# Meshtastic-DIY.net
KiCad netlist of a schematic drawn in EAGLE
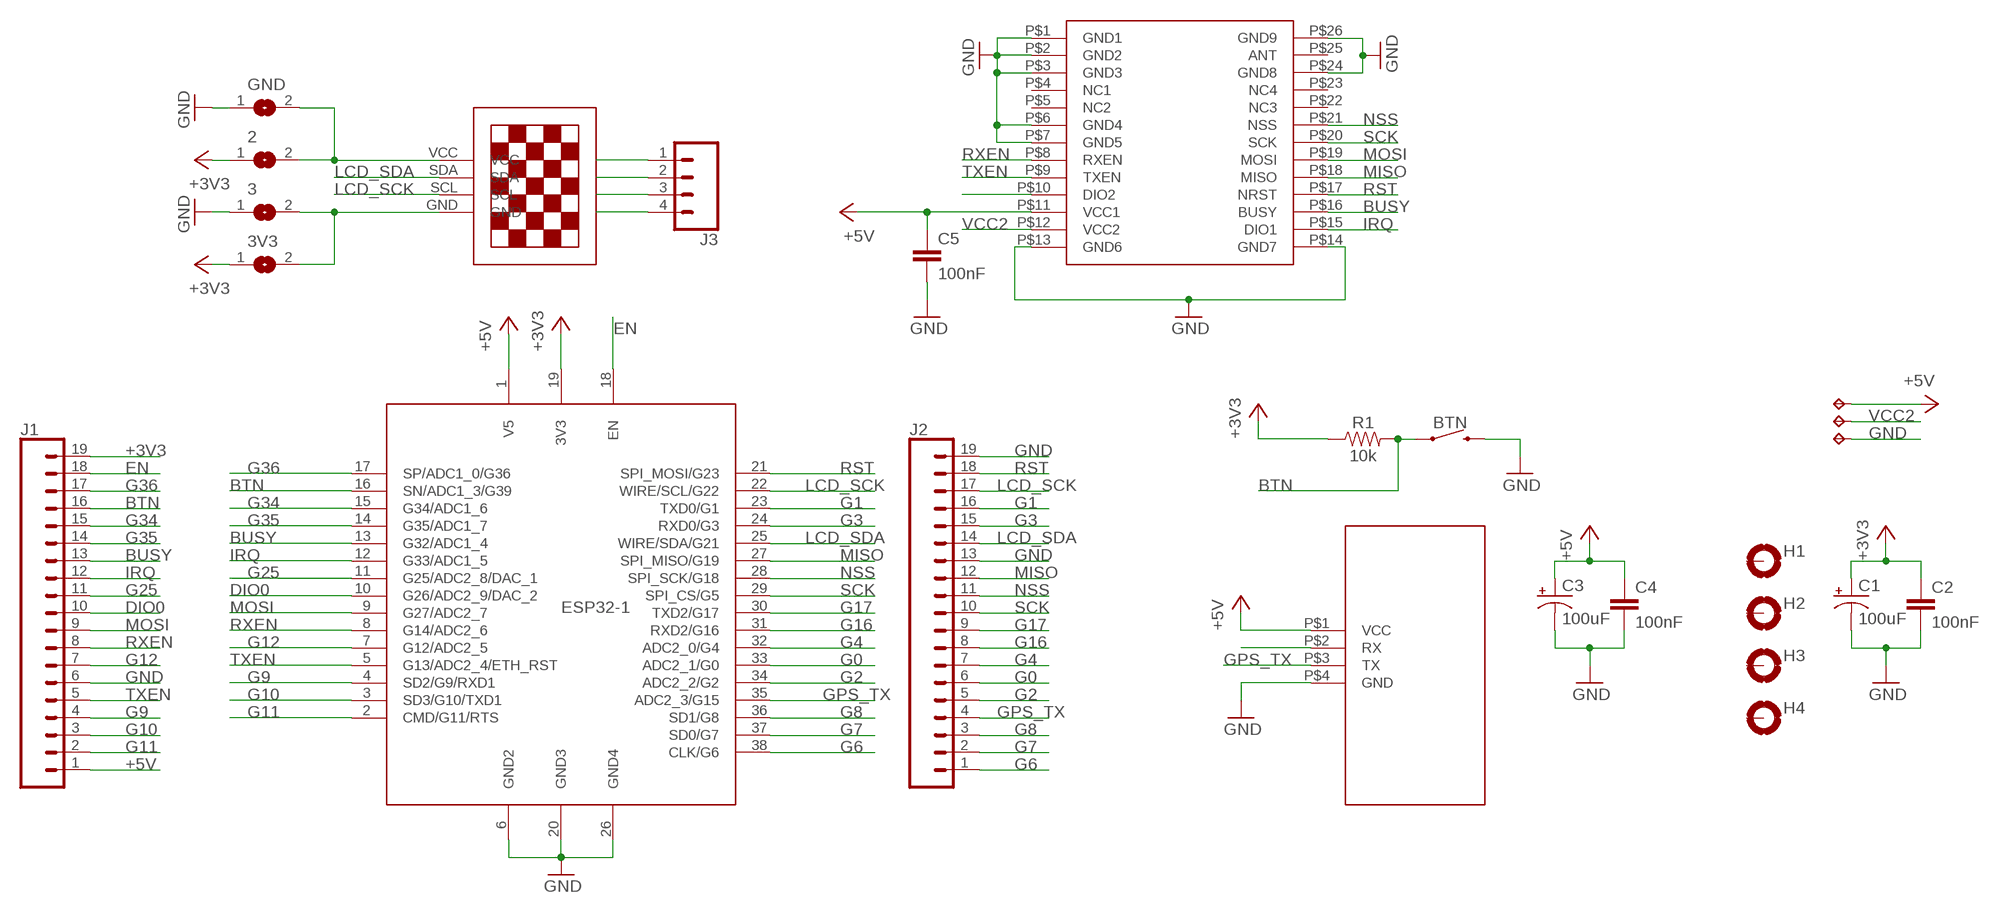
[diagram p0: schematic, sheet 1]

(export (version "E")
  (design (tool "Eeschema 10.0.6"))
  (components
    (comp (ref "2") (value "SJ") (footprint "eagle-import:SJ") (libsource (lib "eagle-import") (part "SJ")))
    (comp (ref "3") (value "SJ") (footprint "eagle-import:SJ") (libsource (lib "eagle-import") (part "SJ")))
    (comp (ref "3V3") (value "SJ") (footprint "eagle-import:SJ") (libsource (lib "eagle-import") (part "SJ")))
    (comp (ref "BTN")
      (value "MOMENTARY-SWITCH-SPST-PTH-6.0MM")
      (footprint "eagle-import:TACTILE_SWITCH_PTH_6.0MM")
      (libsource (lib "eagle-import") (part "MOMENTARY-SWITCH-SPST-PTH-6.0MM"))
    )
    (comp (ref "C1")
      (value "100uF")
      (footprint "eagle-import:EIA7343")
      (libsource (lib "eagle-import") (part "100UF-POLAR-EIA7343-10V-10%(TANT)"))
    )
    (comp (ref "C2")
      (value "100nF")
      (footprint "eagle-import:0805")
      (libsource (lib "eagle-import") (part "0.33UF/330NF-0805-50V-10%"))
    )
    (comp (ref "C3")
      (value "100uF")
      (footprint "eagle-import:EIA7343")
      (libsource (lib "eagle-import") (part "100UF-POLAR-EIA7343-10V-10%(TANT)"))
    )
    (comp (ref "C4")
      (value "100nF")
      (footprint "eagle-import:0805")
      (libsource (lib "eagle-import") (part "0.33UF/330NF-0805-50V-10%"))
    )
    (comp (ref "C5")
      (value "100nF")
      (footprint "eagle-import:0805")
      (libsource (lib "eagle-import") (part "0.33UF/330NF-0805-50V-10%"))
    )
    (comp (ref "ESP32-1")
      (value "NODEMCU_ESP32_WROOM_32")
      (footprint "eagle-import:NODEMCU_ESP32_WROOM_32--38PINS")
      (libsource (lib "eagle-import") (part "NODEMCU_ESP32_WROOM_32"))
    )
    (comp (ref "GND") (value "SJ") (footprint "eagle-import:SJ") (libsource (lib "eagle-import") (part "SJ")))
    (comp (ref "H1")
      (value "MOUNT-PAD-ROUND3.2")
      (footprint "eagle-import:3,2-PAD")
      (libsource (lib "eagle-import") (part "MOUNT-PAD-ROUND3.2"))
    )
    (comp (ref "H2")
      (value "MOUNT-PAD-ROUND3.2")
      (footprint "eagle-import:3,2-PAD")
      (libsource (lib "eagle-import") (part "MOUNT-PAD-ROUND3.2"))
    )
    (comp (ref "H3")
      (value "MOUNT-PAD-ROUND3.2")
      (footprint "eagle-import:3,2-PAD")
      (libsource (lib "eagle-import") (part "MOUNT-PAD-ROUND3.2"))
    )
    (comp (ref "H4")
      (value "MOUNT-PAD-ROUND3.2")
      (footprint "eagle-import:3,2-PAD")
      (libsource (lib "eagle-import") (part "MOUNT-PAD-ROUND3.2"))
    )
    (comp (ref "J1")
      (value "CONN_191X19_NO_SILK")
      (footprint "eagle-import:1X19_NO_SILK")
      (libsource (lib "eagle-import") (part "CONN_191X19_NO_SILK"))
    )
    (comp (ref "J2")
      (value "CONN_191X19_NO_SILK")
      (footprint "eagle-import:1X19_NO_SILK")
      (libsource (lib "eagle-import") (part "CONN_191X19_NO_SILK"))
    )
    (comp (ref "J3")
      (value "CONN_041X04_NO_SILK")
      (footprint "eagle-import:1X04_NO_SILK")
      (libsource (lib "eagle-import") (part "CONN_041X04_NO_SILK"))
    )
    (comp (ref "R1")
      (value "10k")
      (footprint "eagle-import:1210")
      (libsource (lib "eagle-import") (part "0.1OHM-1210-1/2W-1%"))
    )
    (comp (ref "TP1")
      (value "TPTP14SQ")
      (footprint "eagle-import:TP14SQ")
      (libsource (lib "eagle-import") (part "TPTP14SQ"))
    )
    (comp (ref "TP2")
      (value "TPTP14SQ")
      (footprint "eagle-import:TP14SQ")
      (libsource (lib "eagle-import") (part "TPTP14SQ"))
    )
    (comp (ref "TP3")
      (value "TPTP14SQ")
      (footprint "eagle-import:TP14SQ")
      (libsource (lib "eagle-import") (part "TPTP14SQ"))
    )
    (comp (ref "U$1")
      (value "13\"OLED13\"OLED")
      (footprint "eagle-import:1.3_OLED")
      (libsource (lib "eagle-import") (part "13{dblquote}OLED13{dblquote}OLED"))
    )
    (comp (ref "U$2")
      (value "E22-XXXMXXS")
      (footprint "eagle-import:E22-XXXMXXS")
      (libsource (lib "eagle-import") (part "E22-XXXMXXS"))
    )
    (comp (ref "U$3")
      (value "GPS-NEO")
      (footprint "eagle-import:GPS-NEO")
      (libsource (lib "eagle-import") (part "GPS-NEO"))
    )
  )
  (nets
    (net (code "1") (name "+3V3") (class "Default")
      (node (ref "2") (pin "1") (pinfunction "1_1") (pintype "passive"))
      (node (ref "3V3") (pin "1") (pinfunction "1_1") (pintype "passive"))
      (node (ref "C1") (pin "A") (pinfunction "+_A") (pintype "passive"))
      (node (ref "C2") (pin "1") (pinfunction "1_1") (pintype "passive"))
      (node (ref "ESP32-1") (pin "19") (pinfunction "3V3_19") (pintype "power_in"))
      (node (ref "J1") (pin "19") (pinfunction "19_19") (pintype "passive"))
      (node (ref "R1") (pin "1") (pinfunction "1_1") (pintype "passive"))
    )
    (net (code "2") (name "+5V") (class "Default")
      (node (ref "C3") (pin "A") (pinfunction "+_A") (pintype "passive"))
      (node (ref "C4") (pin "1") (pinfunction "1_1") (pintype "passive"))
      (node (ref "C5") (pin "1") (pinfunction "1_1") (pintype "passive"))
      (node (ref "ESP32-1") (pin "1") (pinfunction "V5_1") (pintype "power_in"))
      (node (ref "J1") (pin "1") (pinfunction "1_1") (pintype "passive"))
      (node (ref "TP1") (pin "TP") (pinfunction "TP_TP") (pintype "input"))
      (node (ref "U$2") (pin "P$11") (pinfunction "VCC1_P$11") (pintype "bidirectional"))
      (node (ref "U$3") (pin "P$1") (pinfunction "VCC_P$1") (pintype "bidirectional"))
    )
    (net (code "3") (name "/BTN") (class "Default")
      (node (ref "BTN") (pin "1") (pinfunction "1_1") (pintype "passive"))
      (node (ref "ESP32-1") (pin "16") (pinfunction "SN/ADC1_3/G39_16") (pintype "bidirectional"))
      (node (ref "J1") (pin "16") (pinfunction "16_16") (pintype "passive"))
      (node (ref "R1") (pin "2") (pinfunction "2_2") (pintype "passive"))
    )
    (net (code "4") (name "/BUSY") (class "Default")
      (node (ref "ESP32-1") (pin "13") (pinfunction "G32/ADC1_4_13") (pintype "bidirectional"))
      (node (ref "J1") (pin "13") (pinfunction "13_13") (pintype "passive"))
      (node (ref "U$2") (pin "P$16") (pinfunction "BUSY_P$16") (pintype "bidirectional"))
    )
    (net (code "5") (name "/DIO0") (class "Default")
      (node (ref "ESP32-1") (pin "10") (pinfunction "G26/ADC2_9/DAC_2_10") (pintype "bidirectional"))
      (node (ref "J1") (pin "10") (pinfunction "10_10") (pintype "passive"))
    )
    (net (code "6") (name "/EN") (class "Default")
      (node (ref "ESP32-1") (pin "18") (pinfunction "EN_18") (pintype "bidirectional"))
      (node (ref "J1") (pin "18") (pinfunction "18_18") (pintype "passive"))
    )
    (net (code "7") (name "/G0") (class "Default")
      (node (ref "ESP32-1") (pin "33") (pinfunction "ADC2_1/G0_33") (pintype "bidirectional"))
      (node (ref "J2") (pin "6") (pinfunction "6_6") (pintype "passive"))
    )
    (net (code "8") (name "/G1") (class "Default")
      (node (ref "ESP32-1") (pin "23") (pinfunction "TXD0/G1_23") (pintype "bidirectional"))
      (node (ref "J2") (pin "16") (pinfunction "16_16") (pintype "passive"))
    )
    (net (code "9") (name "/G2") (class "Default")
      (node (ref "ESP32-1") (pin "34") (pinfunction "ADC2_2/G2_34") (pintype "bidirectional"))
      (node (ref "J2") (pin "5") (pinfunction "5_5") (pintype "passive"))
    )
    (net (code "10") (name "/G3") (class "Default")
      (node (ref "ESP32-1") (pin "24") (pinfunction "RXD0/G3_24") (pintype "bidirectional"))
      (node (ref "J2") (pin "15") (pinfunction "15_15") (pintype "passive"))
    )
    (net (code "11") (name "/G4") (class "Default")
      (node (ref "ESP32-1") (pin "32") (pinfunction "ADC2_0/G4_32") (pintype "bidirectional"))
      (node (ref "J2") (pin "7") (pinfunction "7_7") (pintype "passive"))
    )
    (net (code "12") (name "/G6") (class "Default")
      (node (ref "ESP32-1") (pin "38") (pinfunction "CLK/G6_38") (pintype "bidirectional"))
      (node (ref "J2") (pin "1") (pinfunction "1_1") (pintype "passive"))
    )
    (net (code "13") (name "/G7") (class "Default")
      (node (ref "ESP32-1") (pin "37") (pinfunction "SD0/G7_37") (pintype "bidirectional"))
      (node (ref "J2") (pin "2") (pinfunction "2_2") (pintype "passive"))
    )
    (net (code "14") (name "/G8") (class "Default")
      (node (ref "ESP32-1") (pin "36") (pinfunction "SD1/G8_36") (pintype "bidirectional"))
      (node (ref "J2") (pin "3") (pinfunction "3_3") (pintype "passive"))
    )
    (net (code "15") (name "/G9") (class "Default")
      (node (ref "ESP32-1") (pin "4") (pinfunction "SD2/G9/RXD1_4") (pintype "bidirectional"))
      (node (ref "J1") (pin "4") (pinfunction "4_4") (pintype "passive"))
    )
    (net (code "16") (name "/G10") (class "Default")
      (node (ref "ESP32-1") (pin "3") (pinfunction "SD3/G10/TXD1_3") (pintype "bidirectional"))
      (node (ref "J1") (pin "3") (pinfunction "3_3") (pintype "passive"))
    )
    (net (code "17") (name "/G11") (class "Default")
      (node (ref "ESP32-1") (pin "2") (pinfunction "CMD/G11/RTS_2") (pintype "power_in"))
      (node (ref "J1") (pin "2") (pinfunction "2_2") (pintype "passive"))
    )
    (net (code "18") (name "/G12") (class "Default")
      (node (ref "ESP32-1") (pin "7") (pinfunction "G12/ADC2_5_7") (pintype "bidirectional"))
      (node (ref "J1") (pin "7") (pinfunction "7_7") (pintype "passive"))
    )
    (net (code "19") (name "/G16") (class "Default")
      (node (ref "ESP32-1") (pin "31") (pinfunction "RXD2/G16_31") (pintype "bidirectional"))
      (node (ref "J2") (pin "8") (pinfunction "8_8") (pintype "passive"))
    )
    (net (code "20") (name "/G17") (class "Default")
      (node (ref "ESP32-1") (pin "30") (pinfunction "TXD2/G17_30") (pintype "bidirectional"))
      (node (ref "J2") (pin "9") (pinfunction "9_9") (pintype "passive"))
    )
    (net (code "21") (name "/G25") (class "Default")
      (node (ref "ESP32-1") (pin "11") (pinfunction "G25/ADC2_8/DAC_1_11") (pintype "bidirectional"))
      (node (ref "J1") (pin "11") (pinfunction "11_11") (pintype "passive"))
    )
    (net (code "22") (name "/G34") (class "Default")
      (node (ref "ESP32-1") (pin "15") (pinfunction "G34/ADC1_6_15") (pintype "bidirectional"))
      (node (ref "J1") (pin "15") (pinfunction "15_15") (pintype "passive"))
    )
    (net (code "23") (name "/G35") (class "Default")
      (node (ref "ESP32-1") (pin "14") (pinfunction "G35/ADC1_7_14") (pintype "bidirectional"))
      (node (ref "J1") (pin "14") (pinfunction "14_14") (pintype "passive"))
    )
    (net (code "24") (name "/G36") (class "Default")
      (node (ref "ESP32-1") (pin "17") (pinfunction "SP/ADC1_0/G36_17") (pintype "bidirectional"))
      (node (ref "J1") (pin "17") (pinfunction "17_17") (pintype "passive"))
    )
    (net (code "25") (name "/GPS_TX") (class "Default")
      (node (ref "ESP32-1") (pin "35") (pinfunction "ADC2_3/G15_35") (pintype "bidirectional"))
      (node (ref "J2") (pin "4") (pinfunction "4_4") (pintype "passive"))
      (node (ref "U$3") (pin "P$3") (pinfunction "TX_P$3") (pintype "bidirectional"))
    )
    (net (code "26") (name "/IRQ") (class "Default")
      (node (ref "ESP32-1") (pin "12") (pinfunction "G33/ADC1_5_12") (pintype "bidirectional"))
      (node (ref "J1") (pin "12") (pinfunction "12_12") (pintype "passive"))
      (node (ref "U$2") (pin "P$15") (pinfunction "DIO1_P$15") (pintype "bidirectional"))
    )
    (net (code "27") (name "/LCD_SCK") (class "Default")
      (node (ref "ESP32-1") (pin "22") (pinfunction "WIRE/SCL/G22_22") (pintype "bidirectional"))
      (node (ref "J2") (pin "17") (pinfunction "17_17") (pintype "passive"))
      (node (ref "J3") (pin "3") (pinfunction "3_3") (pintype "passive"))
      (node (ref "U$1") (pin "SCL") (pinfunction "SCL_SCL") (pintype "bidirectional"))
    )
    (net (code "28") (name "/LCD_SDA") (class "Default")
      (node (ref "ESP32-1") (pin "25") (pinfunction "WIRE/SDA/G21_25") (pintype "bidirectional"))
      (node (ref "J2") (pin "14") (pinfunction "14_14") (pintype "passive"))
      (node (ref "J3") (pin "4") (pinfunction "4_4") (pintype "passive"))
      (node (ref "U$1") (pin "SDA") (pinfunction "SDA_SDA") (pintype "bidirectional"))
    )
    (net (code "29") (name "/MISO") (class "Default")
      (node (ref "ESP32-1") (pin "27") (pinfunction "SPI_MISO/G19_27") (pintype "bidirectional"))
      (node (ref "J2") (pin "12") (pinfunction "12_12") (pintype "passive"))
      (node (ref "U$2") (pin "P$18") (pinfunction "MISO_P$18") (pintype "bidirectional"))
    )
    (net (code "30") (name "/MOSI") (class "Default")
      (node (ref "ESP32-1") (pin "9") (pinfunction "G27/ADC2_7_9") (pintype "bidirectional"))
      (node (ref "J1") (pin "9") (pinfunction "9_9") (pintype "passive"))
      (node (ref "U$2") (pin "P$19") (pinfunction "MOSI_P$19") (pintype "bidirectional"))
    )
    (net (code "31") (name "/N$2") (class "Default")
      (node (ref "3") (pin "2") (pinfunction "2_2") (pintype "passive"))
      (node (ref "3V3") (pin "2") (pinfunction "2_2") (pintype "passive"))
      (node (ref "J3") (pin "2") (pinfunction "2_2") (pintype "passive"))
      (node (ref "U$1") (pin "GND") (pinfunction "GND_GND") (pintype "bidirectional"))
    )
    (net (code "32") (name "/N$4") (class "Default")
      (node (ref "2") (pin "2") (pinfunction "2_2") (pintype "passive"))
      (node (ref "GND") (pin "2") (pinfunction "2_2") (pintype "passive"))
      (node (ref "J3") (pin "1") (pinfunction "1_1") (pintype "passive"))
      (node (ref "U$1") (pin "VCC") (pinfunction "VCC_VCC") (pintype "bidirectional"))
    )
    (net (code "33") (name "/NSS") (class "Default")
      (node (ref "ESP32-1") (pin "28") (pinfunction "SPI_SCK/G18_28") (pintype "bidirectional"))
      (node (ref "J2") (pin "11") (pinfunction "11_11") (pintype "passive"))
      (node (ref "U$2") (pin "P$21") (pinfunction "NSS_P$21") (pintype "bidirectional"))
    )
    (net (code "34") (name "/RST") (class "Default")
      (node (ref "ESP32-1") (pin "21") (pinfunction "SPI_MOSI/G23_21") (pintype "bidirectional"))
      (node (ref "J2") (pin "18") (pinfunction "18_18") (pintype "passive"))
      (node (ref "U$2") (pin "P$17") (pinfunction "NRST_P$17") (pintype "bidirectional"))
    )
    (net (code "35") (name "/RXEN") (class "Default")
      (node (ref "ESP32-1") (pin "8") (pinfunction "G14/ADC2_6_8") (pintype "bidirectional"))
      (node (ref "J1") (pin "8") (pinfunction "8_8") (pintype "passive"))
      (node (ref "U$2") (pin "P$8") (pinfunction "RXEN_P$8") (pintype "bidirectional"))
    )
    (net (code "36") (name "/SCK") (class "Default")
      (node (ref "ESP32-1") (pin "29") (pinfunction "SPI_CS/G5_29") (pintype "bidirectional"))
      (node (ref "J2") (pin "10") (pinfunction "10_10") (pintype "passive"))
      (node (ref "U$2") (pin "P$20") (pinfunction "SCK_P$20") (pintype "bidirectional"))
    )
    (net (code "37") (name "/TXEN") (class "Default")
      (node (ref "ESP32-1") (pin "5") (pinfunction "G13/ADC2_4/ETH_RST_5") (pintype "bidirectional"))
      (node (ref "J1") (pin "5") (pinfunction "5_5") (pintype "passive"))
      (node (ref "U$2") (pin "P$9") (pinfunction "TXEN_P$9") (pintype "bidirectional"))
    )
    (net (code "38") (name "/VCC2") (class "Default")
      (node (ref "TP2") (pin "TP") (pinfunction "TP_TP") (pintype "input"))
      (node (ref "U$2") (pin "P$12") (pinfunction "VCC2_P$12") (pintype "bidirectional"))
    )
    (net (code "39") (name "GND") (class "Default")
      (node (ref "3") (pin "1") (pinfunction "1_1") (pintype "passive"))
      (node (ref "BTN") (pin "3") (pinfunction "2_3") (pintype "passive"))
      (node (ref "C1") (pin "C") (pinfunction "-_C") (pintype "passive"))
      (node (ref "C2") (pin "2") (pinfunction "2_2") (pintype "passive"))
      (node (ref "C3") (pin "C") (pinfunction "-_C") (pintype "passive"))
      (node (ref "C4") (pin "2") (pinfunction "2_2") (pintype "passive"))
      (node (ref "C5") (pin "2") (pinfunction "2_2") (pintype "passive"))
      (node (ref "ESP32-1") (pin "20") (pinfunction "GND3_20") (pintype "power_in"))
      (node (ref "ESP32-1") (pin "26") (pinfunction "GND4_26") (pintype "power_in"))
      (node (ref "ESP32-1") (pin "6") (pinfunction "GND2_6") (pintype "power_in"))
      (node (ref "GND") (pin "1") (pinfunction "1_1") (pintype "passive"))
      (node (ref "J1") (pin "6") (pinfunction "6_6") (pintype "passive"))
      (node (ref "J2") (pin "13") (pinfunction "13_13") (pintype "passive"))
      (node (ref "J2") (pin "19") (pinfunction "19_19") (pintype "passive"))
      (node (ref "TP3") (pin "TP") (pinfunction "TP_TP") (pintype "input"))
      (node (ref "U$2") (pin "P$1") (pinfunction "GND1_P$1") (pintype "bidirectional"))
      (node (ref "U$2") (pin "P$13") (pinfunction "GND6_P$13") (pintype "bidirectional"))
      (node (ref "U$2") (pin "P$14") (pinfunction "GND7_P$14") (pintype "bidirectional"))
      (node (ref "U$2") (pin "P$2") (pinfunction "GND2_P$2") (pintype "bidirectional"))
      (node (ref "U$2") (pin "P$24") (pinfunction "GND8_P$24") (pintype "bidirectional"))
      (node (ref "U$2") (pin "P$26") (pinfunction "GND9_P$26") (pintype "bidirectional"))
      (node (ref "U$2") (pin "P$3") (pinfunction "GND3_P$3") (pintype "bidirectional"))
      (node (ref "U$2") (pin "P$6") (pinfunction "GND4_P$6") (pintype "bidirectional"))
      (node (ref "U$2") (pin "P$7") (pinfunction "GND5_P$7") (pintype "bidirectional"))
      (node (ref "U$3") (pin "P$4") (pinfunction "GND_P$4") (pintype "bidirectional"))
    )
    (net (code "40") (name "unconnected-(H1-MOUNT-PadB3,2)") (class "Default")
      (node (ref "H1") (pin "B3,2") (pinfunction "MOUNT_B3,2") (pintype "passive"))
    )
    (net (code "41") (name "unconnected-(H2-MOUNT-PadB3,2)") (class "Default")
      (node (ref "H2") (pin "B3,2") (pinfunction "MOUNT_B3,2") (pintype "passive"))
    )
    (net (code "42") (name "unconnected-(H3-MOUNT-PadB3,2)") (class "Default")
      (node (ref "H3") (pin "B3,2") (pinfunction "MOUNT_B3,2") (pintype "passive"))
    )
    (net (code "43") (name "unconnected-(H4-MOUNT-PadB3,2)") (class "Default")
      (node (ref "H4") (pin "B3,2") (pinfunction "MOUNT_B3,2") (pintype "passive"))
    )
    (net (code "44") (name "unconnected-(U$2-ANT-PadP$25)") (class "Default")
      (node (ref "U$2") (pin "P$25") (pinfunction "ANT_P$25") (pintype "bidirectional"))
    )
    (net (code "45") (name "unconnected-(U$2-DIO2-PadP$10)") (class "Default")
      (node (ref "U$2") (pin "P$10") (pinfunction "DIO2_P$10") (pintype "bidirectional"))
    )
    (net (code "46") (name "unconnected-(U$2-NC1-PadP$4)") (class "Default")
      (node (ref "U$2") (pin "P$4") (pinfunction "NC1_P$4") (pintype "bidirectional"))
    )
    (net (code "47") (name "unconnected-(U$2-NC2-PadP$5)") (class "Default")
      (node (ref "U$2") (pin "P$5") (pinfunction "NC2_P$5") (pintype "bidirectional"))
    )
    (net (code "48") (name "unconnected-(U$2-NC3-PadP$22)") (class "Default")
      (node (ref "U$2") (pin "P$22") (pinfunction "NC3_P$22") (pintype "bidirectional"))
    )
    (net (code "49") (name "unconnected-(U$2-NC4-PadP$23)") (class "Default")
      (node (ref "U$2") (pin "P$23") (pinfunction "NC4_P$23") (pintype "bidirectional"))
    )
    (net (code "50") (name "unconnected-(U$3-RX-PadP$2)") (class "Default")
      (node (ref "U$3") (pin "P$2") (pinfunction "RX_P$2") (pintype "bidirectional"))
    )
  )
)
